# DRIVER_GATE_BOARD_solar_boost_converter.net
KiCad netlist of a schematic drawn in Altium Designer
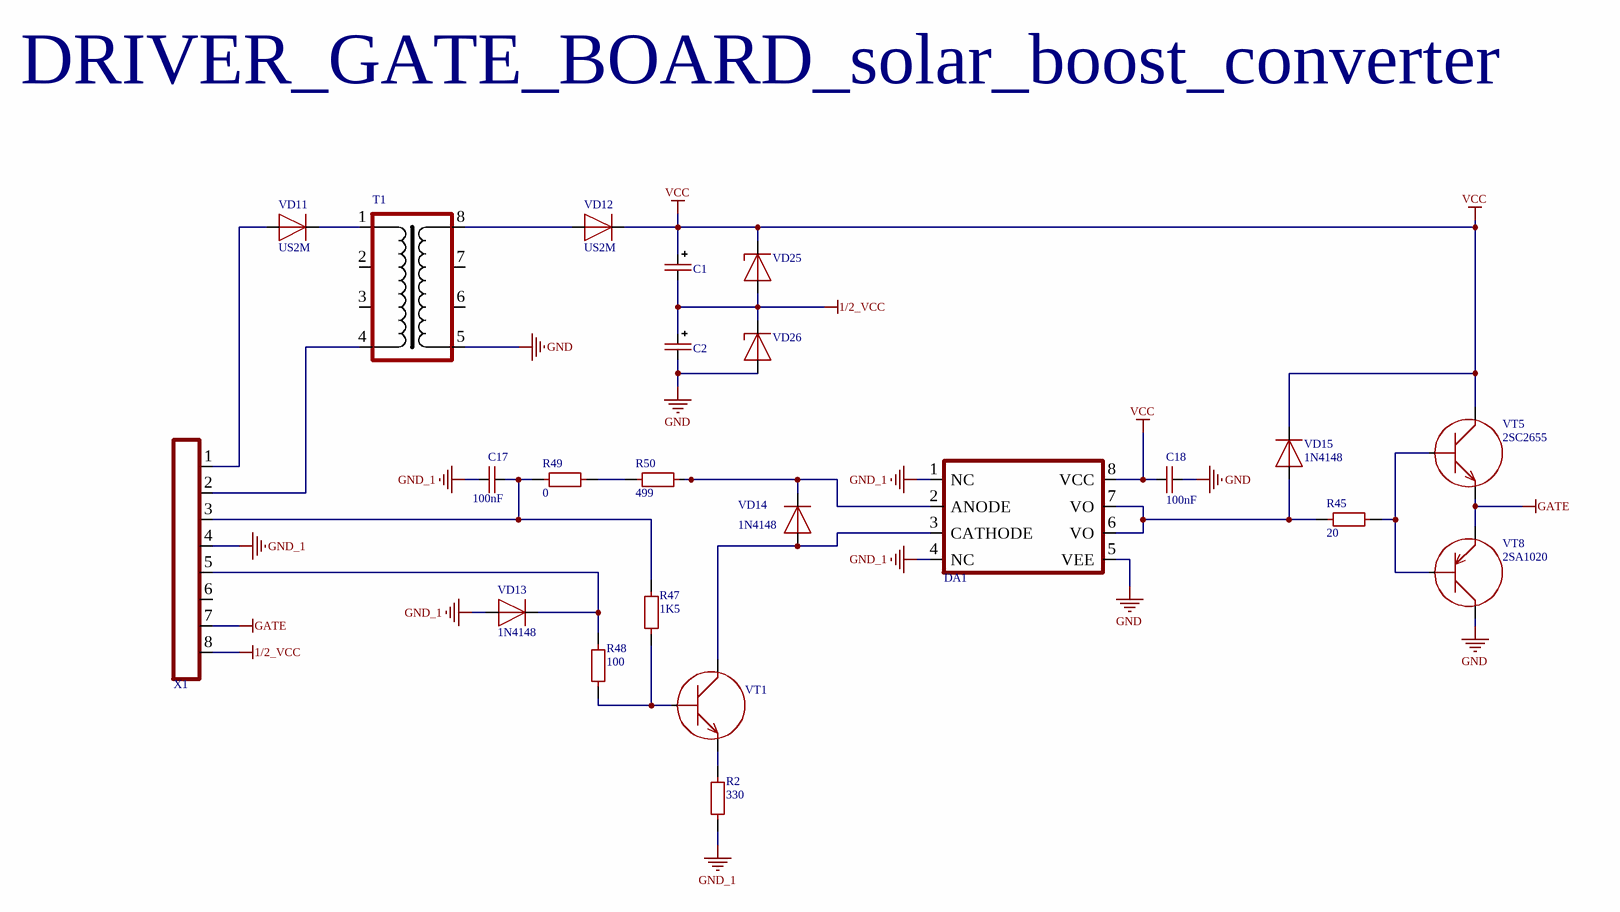
[diagram p0: DRIVER_GATE_BOARD_solar_boost_converter.SchDoc]

(export (version "E")
  (design (tool "Eeschema 10.0.6"))
  (components
    (comp (ref "C1")
      (value "CAP-POLAR")
      (footprint "CAP-TAN-C")
      (libsource (lib "PAS_COMPONENTS") (part "CAP-POLAR"))
    )
    (comp (ref "C2")
      (value "CAP-POLAR")
      (footprint "CAP-TAN-C")
      (libsource (lib "PAS_COMPONENTS") (part "CAP-POLAR"))
    )
    (comp (ref "C17")
      (value "100nF")
      (footprint "CAP-0805")
      (libsource (lib "PAS_COMPONENTS") (part "CAP-NON-POLAR"))
    )
    (comp (ref "C18")
      (value "100nF")
      (footprint "CAP-0805")
      (libsource (lib "PAS_COMPONENTS") (part "CAP-NON-POLAR"))
    )
    (comp (ref "DA1")
      (value "ACPL-T350")
      (footprint "ACPL-T350")
      (libsource (lib "ACPL-T350") (part "ACPL-T350"))
    )
    (comp (ref "R2")
      (value "330")
      (footprint "RES-0805")
      (libsource (lib "PAS_COMPONENTS") (part "RES-CONST"))
    )
    (comp (ref "R45")
      (value "20")
      (footprint "RES-0805")
      (libsource (lib "PAS_COMPONENTS") (part "RES-CONST"))
    )
    (comp (ref "R47")
      (value "1K5")
      (footprint "RES-0805")
      (libsource (lib "PAS_COMPONENTS") (part "RES-CONST"))
    )
    (comp (ref "R48")
      (value "100")
      (footprint "RES-0805")
      (libsource (lib "PAS_COMPONENTS") (part "RES-CONST"))
    )
    (comp (ref "R49")
      (value "0")
      (footprint "RES-0805")
      (libsource (lib "PAS_COMPONENTS") (part "RES-CONST"))
    )
    (comp (ref "R50")
      (value "499")
      (footprint "RES-0805")
      (libsource (lib "PAS_COMPONENTS") (part "RES-CONST"))
    )
    (comp (ref "T1")
      (value "TRANS_EE10")
      (footprint "TRANS_EE10")
      (libsource (lib "TRANS_EE10") (part "TRANS_EE10"))
    )
    (comp (ref "VD11") (value "US2M") (footprint "DO-214AC, SMA") (libsource (lib "DIODES") (part "DIODE")))
    (comp (ref "VD12") (value "US2M") (footprint "DO-214AC, SMA") (libsource (lib "DIODES") (part "DIODE")))
    (comp (ref "VD13") (value "1N4148") (footprint "SOD-123") (libsource (lib "DIODES") (part "DIODE")))
    (comp (ref "VD14") (value "1N4148") (footprint "SOD-123") (libsource (lib "DIODES") (part "DIODE")))
    (comp (ref "VD15") (value "1N4148") (footprint "SOD-123") (libsource (lib "DIODES") (part "DIODE")))
    (comp (ref "VD25") (value "~") (footprint "SOD-80") (libsource (lib "DIODES") (part "ZENER")))
    (comp (ref "VD26") (value "~") (footprint "SOD-80") (libsource (lib "DIODES") (part "ZENER")))
    (comp (ref "VT1") (value "BC847-BEC") (footprint "SOT23-3") (libsource (lib "BC8XX") (part "BC847-BEC")))
    (comp (ref "VT5")
      (value "2SC2655")
      (footprint "SOT-89")
      (libsource (lib "TRANSISTORS") (part "BIPOLAR-NPN-BEC"))
    )
    (comp (ref "VT8")
      (value "2SA1020")
      (footprint "SOT-89")
      (libsource (lib "TRANSISTORS") (part "BIPOLAR-PNP-BCE"))
    )
    (comp (ref "X1")
      (value "CONN-8-PIN")
      (footprint "CONN-PLS-8-2.54mm")
      (libsource (lib "CONN_PLS") (part "CONN-8-PIN"))
    )
  )
  (nets
    (net (code "1") (name "1{slash}2_VCC") (class "Default")
      (node (ref "C1") (pin "2") (pinfunction "-_2") (pintype "passive"))
      (node (ref "C2") (pin "1") (pinfunction "+_1") (pintype "passive"))
      (node (ref "VD25") (pin "2") (pinfunction "A_2") (pintype "passive"))
      (node (ref "VD26") (pin "1") (pinfunction "C_1") (pintype "passive"))
      (node (ref "X1") (pin "8") (pinfunction "8_8") (pintype "passive"))
    )
    (net (code "2") (name "GATE") (class "Default")
      (node (ref "VT5") (pin "3") (pinfunction "E_3") (pintype "passive"))
      (node (ref "VT8") (pin "3") (pinfunction "E_3") (pintype "passive"))
      (node (ref "X1") (pin "7") (pinfunction "7_7") (pintype "passive"))
    )
    (net (code "3") (name "GND") (class "Default")
      (node (ref "C18") (pin "2") (pinfunction "2_2") (pintype "passive"))
      (node (ref "C2") (pin "2") (pinfunction "-_2") (pintype "passive"))
      (node (ref "DA1") (pin "5") (pinfunction "VEE_5") (pintype "passive"))
      (node (ref "T1") (pin "5") (pintype "passive"))
      (node (ref "VD26") (pin "2") (pinfunction "A_2") (pintype "passive"))
      (node (ref "VT8") (pin "2") (pinfunction "C_2") (pintype "passive"))
    )
    (net (code "4") (name "GND_1") (class "Default")
      (node (ref "C17") (pin "1") (pinfunction "1_1") (pintype "passive"))
      (node (ref "DA1") (pin "1") (pinfunction "NC_1") (pintype "passive"))
      (node (ref "DA1") (pin "4") (pinfunction "NC_4") (pintype "passive"))
      (node (ref "R2") (pin "2") (pinfunction "2_2") (pintype "passive"))
      (node (ref "VD13") (pin "2") (pinfunction "A_2") (pintype "passive"))
      (node (ref "X1") (pin "4") (pinfunction "4_4") (pintype "passive"))
    )
    (net (code "5") (name "Net-(C17-Pad2)") (class "Default")
      (node (ref "C17") (pin "2") (pinfunction "2_2") (pintype "passive"))
      (node (ref "R47") (pin "2") (pinfunction "2_2") (pintype "passive"))
      (node (ref "R49") (pin "2") (pinfunction "2_2") (pintype "passive"))
      (node (ref "X1") (pin "3") (pinfunction "3_3") (pintype "passive"))
    )
    (net (code "6") (name "Net-(DA1-ANODE)") (class "Default")
      (node (ref "DA1") (pin "2") (pinfunction "ANODE_2") (pintype "passive"))
      (node (ref "R50") (pin "1") (pinfunction "1_1") (pintype "passive"))
      (node (ref "VD14") (pin "1") (pinfunction "C_1") (pintype "passive"))
    )
    (net (code "7") (name "Net-(DA1-CATHODE)") (class "Default")
      (node (ref "DA1") (pin "3") (pinfunction "CATHODE_3") (pintype "passive"))
      (node (ref "VD14") (pin "2") (pinfunction "A_2") (pintype "passive"))
      (node (ref "VT1") (pin "3") (pinfunction "C_3") (pintype "passive"))
    )
    (net (code "8") (name "Net-(R49-Pad1)") (class "Default")
      (node (ref "R49") (pin "1") (pinfunction "1_1") (pintype "passive"))
      (node (ref "R50") (pin "2") (pinfunction "2_2") (pintype "passive"))
    )
    (net (code "9") (name "Net-(T1-Pad4)") (class "Default")
      (node (ref "T1") (pin "4") (pintype "passive"))
      (node (ref "X1") (pin "2") (pinfunction "2_2") (pintype "passive"))
    )
    (net (code "10") (name "Net-(VD11-A)") (class "Default")
      (node (ref "VD11") (pin "2") (pinfunction "A_2") (pintype "passive"))
      (node (ref "X1") (pin "1") (pinfunction "1_1") (pintype "passive"))
    )
    (net (code "11") (name "Net-(VD11-C)") (class "Default")
      (node (ref "T1") (pin "1") (pintype "passive"))
      (node (ref "VD11") (pin "1") (pinfunction "C_1") (pintype "passive"))
    )
    (net (code "12") (name "Net-(VD12-A)") (class "Default")
      (node (ref "T1") (pin "8") (pintype "passive"))
      (node (ref "VD12") (pin "2") (pinfunction "A_2") (pintype "passive"))
    )
    (net (code "13") (name "Net-(VD13-C)") (class "Default")
      (node (ref "R48") (pin "1") (pinfunction "1_1") (pintype "passive"))
      (node (ref "VD13") (pin "1") (pinfunction "C_1") (pintype "passive"))
      (node (ref "X1") (pin "5") (pinfunction "5_5") (pintype "passive"))
    )
    (net (code "14") (name "Net-(VD15-A)") (class "Default")
      (node (ref "DA1") (pin "6") (pinfunction "VO_6") (pintype "passive"))
      (node (ref "DA1") (pin "7") (pinfunction "VO_7") (pintype "passive"))
      (node (ref "R45") (pin "1") (pinfunction "1_1") (pintype "passive"))
      (node (ref "VD15") (pin "2") (pinfunction "A_2") (pintype "passive"))
    )
    (net (code "15") (name "Net-(VT1-B)") (class "Default")
      (node (ref "R47") (pin "1") (pinfunction "1_1") (pintype "passive"))
      (node (ref "R48") (pin "2") (pinfunction "2_2") (pintype "passive"))
      (node (ref "VT1") (pin "1") (pinfunction "B_1") (pintype "passive"))
    )
    (net (code "16") (name "Net-(VT1-E)") (class "Default")
      (node (ref "R2") (pin "1") (pinfunction "1_1") (pintype "passive"))
      (node (ref "VT1") (pin "2") (pinfunction "E_2") (pintype "passive"))
    )
    (net (code "17") (name "Net-(VT5-B)") (class "Default")
      (node (ref "R45") (pin "2") (pinfunction "2_2") (pintype "passive"))
      (node (ref "VT5") (pin "1") (pinfunction "B_1") (pintype "passive"))
      (node (ref "VT8") (pin "1") (pinfunction "B_1") (pintype "passive"))
    )
    (net (code "18") (name "VCC") (class "Default")
      (node (ref "C1") (pin "1") (pinfunction "+_1") (pintype "passive"))
      (node (ref "C18") (pin "1") (pinfunction "1_1") (pintype "passive"))
      (node (ref "DA1") (pin "8") (pinfunction "VCC_8") (pintype "passive"))
      (node (ref "VD12") (pin "1") (pinfunction "C_1") (pintype "passive"))
      (node (ref "VD15") (pin "1") (pinfunction "C_1") (pintype "passive"))
      (node (ref "VD25") (pin "1") (pinfunction "C_1") (pintype "passive"))
      (node (ref "VT5") (pin "2") (pinfunction "C_2") (pintype "passive"))
    )
    (net (code "19") (name "unconnected-(T1-Pad2)") (class "Default")
      (node (ref "T1") (pin "2") (pintype "passive"))
    )
    (net (code "20") (name "unconnected-(T1-Pad3)") (class "Default")
      (node (ref "T1") (pin "3") (pintype "passive"))
    )
    (net (code "21") (name "unconnected-(T1-Pad6)") (class "Default")
      (node (ref "T1") (pin "6") (pintype "passive"))
    )
    (net (code "22") (name "unconnected-(T1-Pad7)") (class "Default")
      (node (ref "T1") (pin "7") (pintype "passive"))
    )
    (net (code "23") (name "unconnected-(X1-Pad6)") (class "Default")
      (node (ref "X1") (pin "6") (pinfunction "6_6") (pintype "passive"))
    )
  )
)
